# LED.net
KiCad netlist of a schematic drawn in Altium Designer
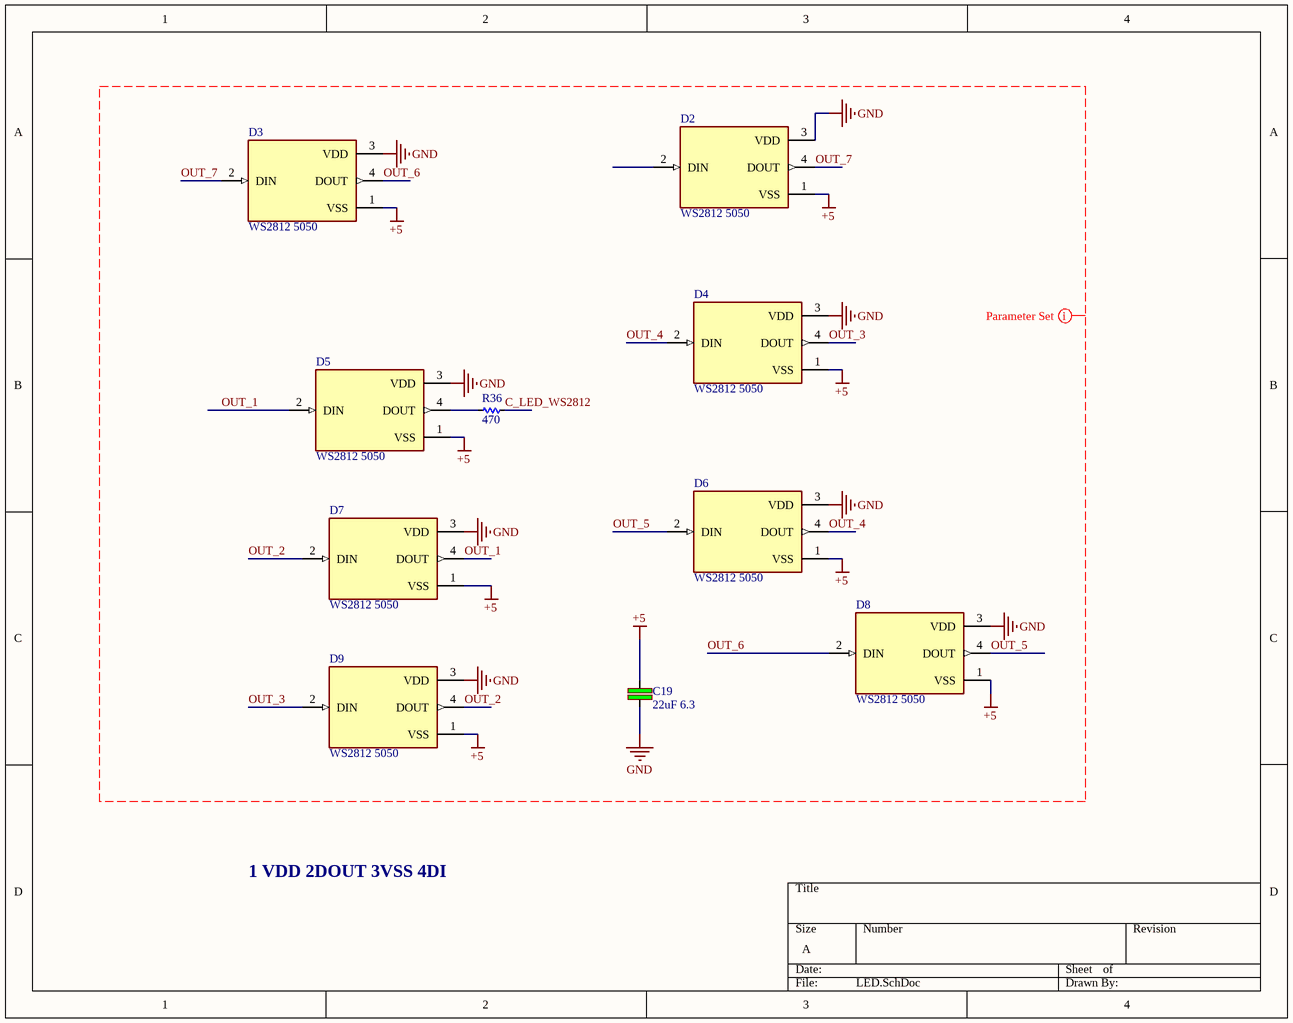
[diagram p0: LED.SchDoc]

(export (version "E")
  (design (tool "Eeschema 10.0.6"))
  (components
    (comp (ref "C19")
      (value "22uF 6.3")
      (footprint "CN-SMD-1206")
      (description "Cap SMD 1206 >5V")
      (libsource (lib "Library AL") (part "C"))
    )
    (comp (ref "D2")
      (value "WS2812 5050")
      (footprint "LED_1655")
      (fields (field (name "MF") "Adafruit Industries") (field (name "MP") "1655"))
      (libsource (lib "1655") (part "1655"))
    )
    (comp (ref "D3")
      (value "WS2812 5050")
      (footprint "LED_1655")
      (fields (field (name "MF") "Adafruit Industries") (field (name "MP") "1655"))
      (libsource (lib "1655") (part "1655"))
    )
    (comp (ref "D4")
      (value "WS2812 5050")
      (footprint "LED_1655")
      (fields (field (name "MF") "Adafruit Industries") (field (name "MP") "1655"))
      (libsource (lib "1655") (part "1655"))
    )
    (comp (ref "D5")
      (value "WS2812 5050")
      (footprint "LED_1655")
      (fields (field (name "MF") "Adafruit Industries") (field (name "MP") "1655"))
      (libsource (lib "1655") (part "1655"))
    )
    (comp (ref "D6")
      (value "WS2812 5050")
      (footprint "LED_1655")
      (fields (field (name "MF") "Adafruit Industries") (field (name "MP") "1655"))
      (libsource (lib "1655") (part "1655"))
    )
    (comp (ref "D7")
      (value "WS2812 5050")
      (footprint "LED_1655")
      (fields (field (name "MF") "Adafruit Industries") (field (name "MP") "1655"))
      (libsource (lib "1655") (part "1655"))
    )
    (comp (ref "D8")
      (value "WS2812 5050")
      (footprint "LED_1655")
      (fields (field (name "MF") "Adafruit Industries") (field (name "MP") "1655"))
      (libsource (lib "1655") (part "1655"))
    )
    (comp (ref "D9")
      (value "WS2812 5050")
      (footprint "LED_1655")
      (fields (field (name "MF") "Adafruit Industries") (field (name "MP") "1655"))
      (libsource (lib "1655") (part "1655"))
    )
    (comp (ref "R36")
      (value "470")
      (footprint "RES-SMD-0603")
      (description "Resistor")
      (fields
        (field (name "MANUFACTURER") "Generic Components")
        (field (name "PUBLISHER") "Altium Hobart Technology Centre")
      )
      (libsource (lib "My Library") (part "Res-SMD"))
    )
  )
  (nets
    (net (code "1") (name "+5") (class "Default")
      (node (ref "C19") (pin "2") (pinfunction "2_2") (pintype "passive"))
      (node (ref "D2") (pin "1") (pinfunction "VSS_1") (pintype "power_in"))
      (node (ref "D3") (pin "1") (pinfunction "VSS_1") (pintype "power_in"))
      (node (ref "D4") (pin "1") (pinfunction "VSS_1") (pintype "power_in"))
      (node (ref "D5") (pin "1") (pinfunction "VSS_1") (pintype "power_in"))
      (node (ref "D6") (pin "1") (pinfunction "VSS_1") (pintype "power_in"))
      (node (ref "D7") (pin "1") (pinfunction "VSS_1") (pintype "power_in"))
      (node (ref "D8") (pin "1") (pinfunction "VSS_1") (pintype "power_in"))
      (node (ref "D9") (pin "1") (pinfunction "VSS_1") (pintype "power_in"))
    )
    (net (code "2") (name "/C_LED_WS2812") (class "Default")
      (node (ref "R36") (pin "1") (pinfunction "1_1") (pintype "passive"))
    )
    (net (code "3") (name "/OUT_1") (class "Default")
      (node (ref "D5") (pin "2") (pinfunction "DIN_2") (pintype "input"))
      (node (ref "D7") (pin "4") (pinfunction "DOUT_4") (pintype "output"))
    )
    (net (code "4") (name "/OUT_2") (class "Default")
      (node (ref "D7") (pin "2") (pinfunction "DIN_2") (pintype "input"))
      (node (ref "D9") (pin "4") (pinfunction "DOUT_4") (pintype "output"))
    )
    (net (code "5") (name "/OUT_3") (class "Default")
      (node (ref "D4") (pin "4") (pinfunction "DOUT_4") (pintype "output"))
      (node (ref "D9") (pin "2") (pinfunction "DIN_2") (pintype "input"))
    )
    (net (code "6") (name "/OUT_4") (class "Default")
      (node (ref "D4") (pin "2") (pinfunction "DIN_2") (pintype "input"))
      (node (ref "D6") (pin "4") (pinfunction "DOUT_4") (pintype "output"))
    )
    (net (code "7") (name "/OUT_5") (class "Default")
      (node (ref "D6") (pin "2") (pinfunction "DIN_2") (pintype "input"))
      (node (ref "D8") (pin "4") (pinfunction "DOUT_4") (pintype "output"))
    )
    (net (code "8") (name "/OUT_6") (class "Default")
      (node (ref "D3") (pin "4") (pinfunction "DOUT_4") (pintype "output"))
      (node (ref "D8") (pin "2") (pinfunction "DIN_2") (pintype "input"))
    )
    (net (code "9") (name "/OUT_7") (class "Default")
      (node (ref "D2") (pin "4") (pinfunction "DOUT_4") (pintype "output"))
      (node (ref "D3") (pin "2") (pinfunction "DIN_2") (pintype "input"))
    )
    (net (code "10") (name "GND") (class "Default")
      (node (ref "C19") (pin "1") (pinfunction "1_1") (pintype "passive"))
      (node (ref "D2") (pin "3") (pinfunction "VDD_3") (pintype "power_in"))
      (node (ref "D3") (pin "3") (pinfunction "VDD_3") (pintype "power_in"))
      (node (ref "D4") (pin "3") (pinfunction "VDD_3") (pintype "power_in"))
      (node (ref "D5") (pin "3") (pinfunction "VDD_3") (pintype "power_in"))
      (node (ref "D6") (pin "3") (pinfunction "VDD_3") (pintype "power_in"))
      (node (ref "D7") (pin "3") (pinfunction "VDD_3") (pintype "power_in"))
      (node (ref "D8") (pin "3") (pinfunction "VDD_3") (pintype "power_in"))
      (node (ref "D9") (pin "3") (pinfunction "VDD_3") (pintype "power_in"))
    )
    (net (code "11") (name "Net-(D5-DOUT)") (class "Default")
      (node (ref "D5") (pin "4") (pinfunction "DOUT_4") (pintype "output"))
      (node (ref "R36") (pin "2") (pinfunction "2_2") (pintype "passive"))
    )
    (net (code "12") (name "unconnected-(D2-DIN-Pad2)") (class "Default")
      (node (ref "D2") (pin "2") (pinfunction "DIN_2") (pintype "input"))
    )
  )
)
